# isd_main_lighting_board-v2.net
KiCad netlist of a schematic drawn in EAGLE
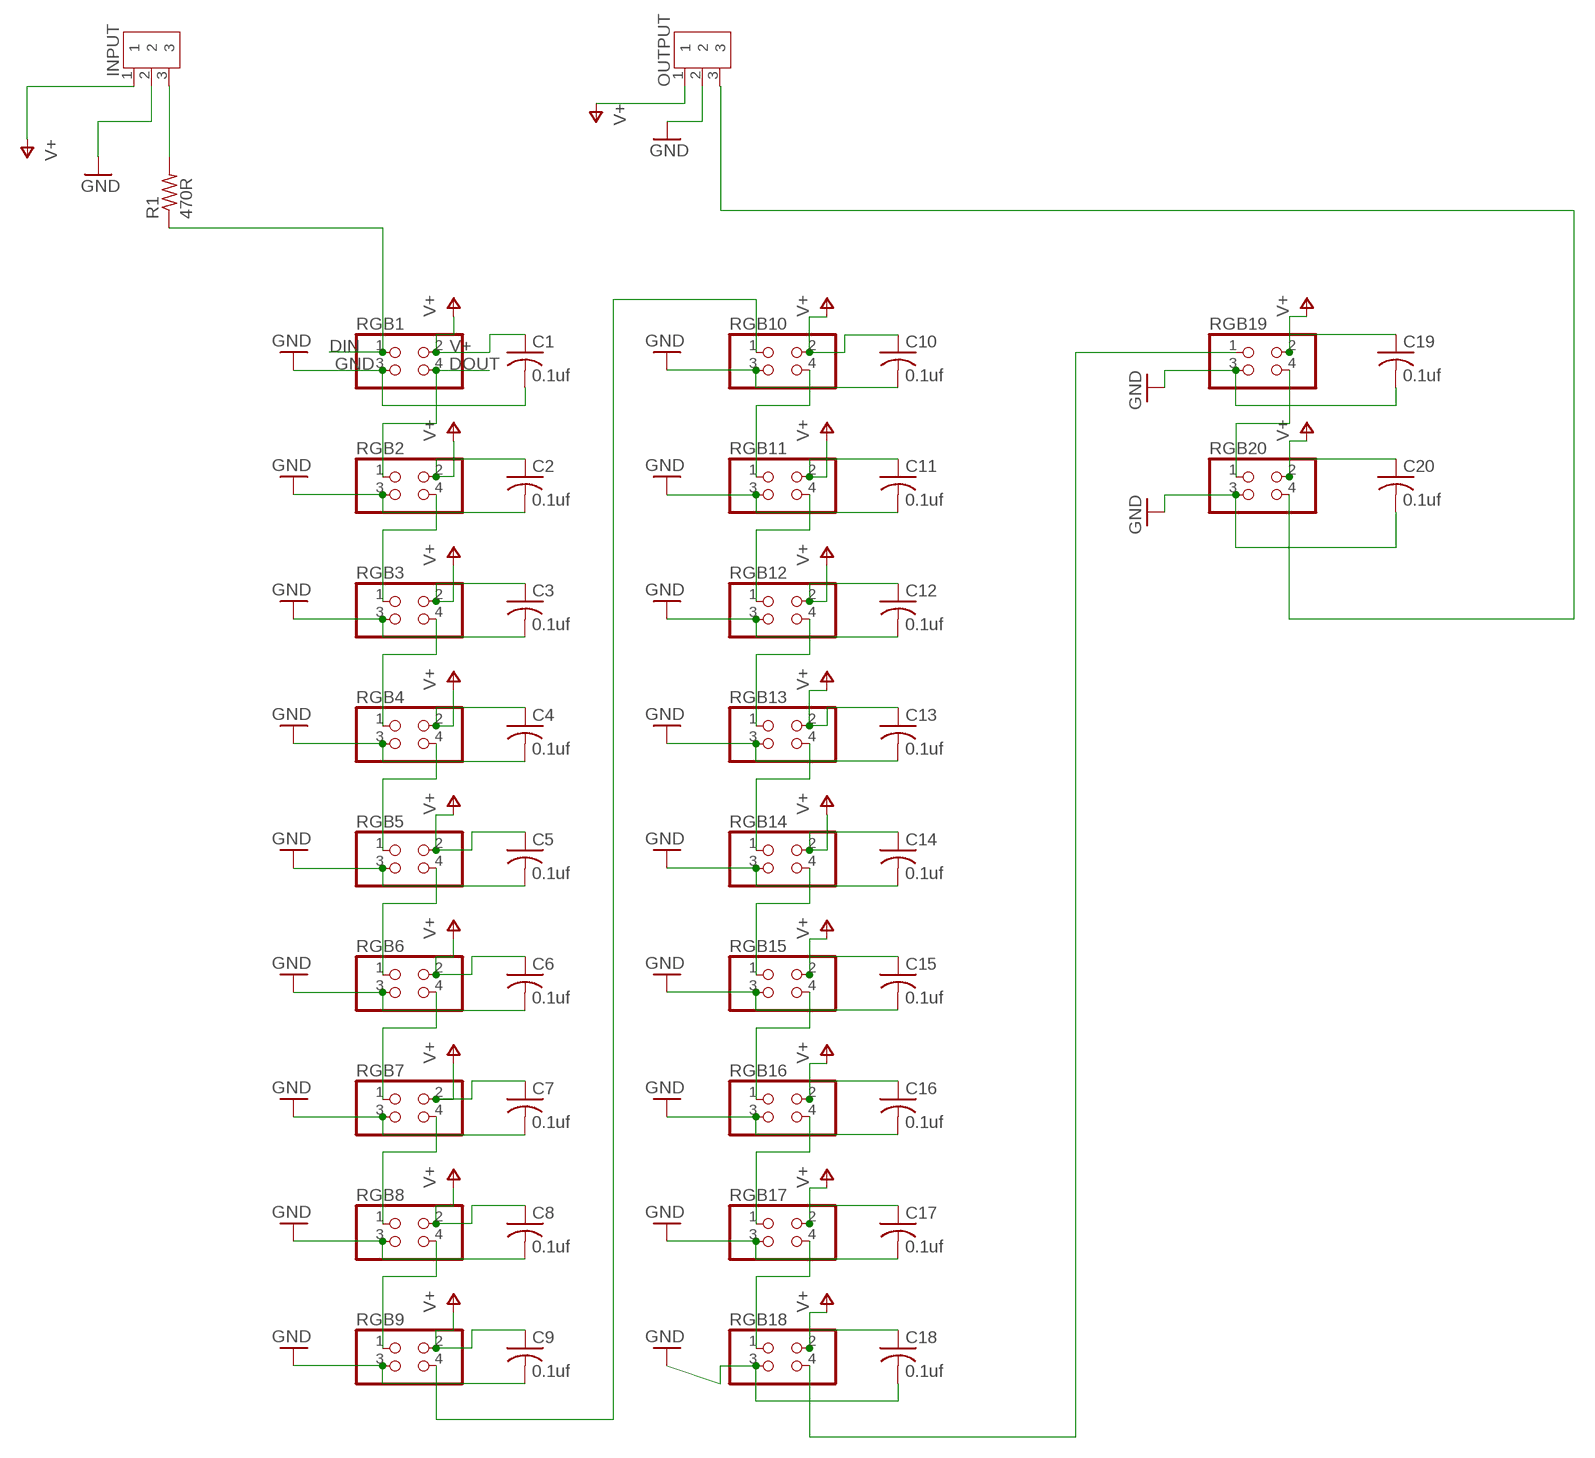
[diagram p0: schematic, sheet 1]

(export (version "E")
  (design (tool "Eeschema 10.0.6"))
  (components
    (comp (ref "C1")
      (value "0.1uf")
      (footprint "eagle-import:C0805")
      (libsource (lib "eagle-import") (part "C-USC0805"))
    )
    (comp (ref "C2")
      (value "0.1uf")
      (footprint "eagle-import:C0805")
      (libsource (lib "eagle-import") (part "C-USC0805"))
    )
    (comp (ref "C3")
      (value "0.1uf")
      (footprint "eagle-import:C0805")
      (libsource (lib "eagle-import") (part "C-USC0805"))
    )
    (comp (ref "C4")
      (value "0.1uf")
      (footprint "eagle-import:C0805")
      (libsource (lib "eagle-import") (part "C-USC0805"))
    )
    (comp (ref "C5")
      (value "0.1uf")
      (footprint "eagle-import:C0805")
      (libsource (lib "eagle-import") (part "C-USC0805"))
    )
    (comp (ref "C6")
      (value "0.1uf")
      (footprint "eagle-import:C0805")
      (libsource (lib "eagle-import") (part "C-USC0805"))
    )
    (comp (ref "C7")
      (value "0.1uf")
      (footprint "eagle-import:C0805")
      (libsource (lib "eagle-import") (part "C-USC0805"))
    )
    (comp (ref "C8")
      (value "0.1uf")
      (footprint "eagle-import:C0805")
      (libsource (lib "eagle-import") (part "C-USC0805"))
    )
    (comp (ref "C9")
      (value "0.1uf")
      (footprint "eagle-import:C0805")
      (libsource (lib "eagle-import") (part "C-USC0805"))
    )
    (comp (ref "C10")
      (value "0.1uf")
      (footprint "eagle-import:C0805")
      (libsource (lib "eagle-import") (part "C-USC0805"))
    )
    (comp (ref "C11")
      (value "0.1uf")
      (footprint "eagle-import:C0805")
      (libsource (lib "eagle-import") (part "C-USC0805"))
    )
    (comp (ref "C12")
      (value "0.1uf")
      (footprint "eagle-import:C0805")
      (libsource (lib "eagle-import") (part "C-USC0805"))
    )
    (comp (ref "C13")
      (value "0.1uf")
      (footprint "eagle-import:C0805")
      (libsource (lib "eagle-import") (part "C-USC0805"))
    )
    (comp (ref "C14")
      (value "0.1uf")
      (footprint "eagle-import:C0805")
      (libsource (lib "eagle-import") (part "C-USC0805"))
    )
    (comp (ref "C15")
      (value "0.1uf")
      (footprint "eagle-import:C0805")
      (libsource (lib "eagle-import") (part "C-USC0805"))
    )
    (comp (ref "C16")
      (value "0.1uf")
      (footprint "eagle-import:C0805")
      (libsource (lib "eagle-import") (part "C-USC0805"))
    )
    (comp (ref "C17")
      (value "0.1uf")
      (footprint "eagle-import:C0805")
      (libsource (lib "eagle-import") (part "C-USC0805"))
    )
    (comp (ref "C18")
      (value "0.1uf")
      (footprint "eagle-import:C0805")
      (libsource (lib "eagle-import") (part "C-USC0805"))
    )
    (comp (ref "C19")
      (value "0.1uf")
      (footprint "eagle-import:C0805")
      (libsource (lib "eagle-import") (part "C-USC0805"))
    )
    (comp (ref "C20")
      (value "0.1uf")
      (footprint "eagle-import:C0805")
      (libsource (lib "eagle-import") (part "C-USC0805"))
    )
    (comp (ref "INPUT")
      (value "B3B-XH-A")
      (footprint "eagle-import:B3B-XH-A")
      (fields (field (name "MANUFACTURER") "JST (XH connector)"))
      (libsource (lib "eagle-import") (part "B3B-XH-A"))
    )
    (comp (ref "OUTPUT")
      (value "B3B-XH-A")
      (footprint "eagle-import:B3B-XH-A")
      (fields (field (name "MANUFACTURER") "JST (XH connector)"))
      (libsource (lib "eagle-import") (part "B3B-XH-A"))
    )
    (comp (ref "R1")
      (value "470R")
      (footprint "eagle-import:0204_5")
      (libsource (lib "eagle-import") (part "R-US_0204/5"))
    )
    (comp (ref "RGB1")
      (value "PINHD-2X2")
      (footprint "eagle-import:2X02")
      (libsource (lib "eagle-import") (part "PINHD-2X2"))
    )
    (comp (ref "RGB2")
      (value "PINHD-2X2")
      (footprint "eagle-import:2X02")
      (libsource (lib "eagle-import") (part "PINHD-2X2"))
    )
    (comp (ref "RGB3")
      (value "PINHD-2X2")
      (footprint "eagle-import:2X02")
      (libsource (lib "eagle-import") (part "PINHD-2X2"))
    )
    (comp (ref "RGB4")
      (value "PINHD-2X2")
      (footprint "eagle-import:2X02")
      (libsource (lib "eagle-import") (part "PINHD-2X2"))
    )
    (comp (ref "RGB5")
      (value "PINHD-2X2")
      (footprint "eagle-import:2X02")
      (libsource (lib "eagle-import") (part "PINHD-2X2"))
    )
    (comp (ref "RGB6")
      (value "PINHD-2X2")
      (footprint "eagle-import:2X02")
      (libsource (lib "eagle-import") (part "PINHD-2X2"))
    )
    (comp (ref "RGB7")
      (value "PINHD-2X2")
      (footprint "eagle-import:2X02")
      (libsource (lib "eagle-import") (part "PINHD-2X2"))
    )
    (comp (ref "RGB8")
      (value "PINHD-2X2")
      (footprint "eagle-import:2X02")
      (libsource (lib "eagle-import") (part "PINHD-2X2"))
    )
    (comp (ref "RGB9")
      (value "PINHD-2X2")
      (footprint "eagle-import:2X02")
      (libsource (lib "eagle-import") (part "PINHD-2X2"))
    )
    (comp (ref "RGB10")
      (value "PINHD-2X2")
      (footprint "eagle-import:2X02")
      (libsource (lib "eagle-import") (part "PINHD-2X2"))
    )
    (comp (ref "RGB11")
      (value "PINHD-2X2")
      (footprint "eagle-import:2X02")
      (libsource (lib "eagle-import") (part "PINHD-2X2"))
    )
    (comp (ref "RGB12")
      (value "PINHD-2X2")
      (footprint "eagle-import:2X02")
      (libsource (lib "eagle-import") (part "PINHD-2X2"))
    )
    (comp (ref "RGB13")
      (value "PINHD-2X2")
      (footprint "eagle-import:2X02")
      (libsource (lib "eagle-import") (part "PINHD-2X2"))
    )
    (comp (ref "RGB14")
      (value "PINHD-2X2")
      (footprint "eagle-import:2X02")
      (libsource (lib "eagle-import") (part "PINHD-2X2"))
    )
    (comp (ref "RGB15")
      (value "PINHD-2X2")
      (footprint "eagle-import:2X02")
      (libsource (lib "eagle-import") (part "PINHD-2X2"))
    )
    (comp (ref "RGB16")
      (value "PINHD-2X2")
      (footprint "eagle-import:2X02")
      (libsource (lib "eagle-import") (part "PINHD-2X2"))
    )
    (comp (ref "RGB17")
      (value "PINHD-2X2")
      (footprint "eagle-import:2X02")
      (libsource (lib "eagle-import") (part "PINHD-2X2"))
    )
    (comp (ref "RGB18")
      (value "PINHD-2X2")
      (footprint "eagle-import:2X02")
      (libsource (lib "eagle-import") (part "PINHD-2X2"))
    )
    (comp (ref "RGB19")
      (value "PINHD-2X2")
      (footprint "eagle-import:2X02")
      (libsource (lib "eagle-import") (part "PINHD-2X2"))
    )
    (comp (ref "RGB20")
      (value "PINHD-2X2")
      (footprint "eagle-import:2X02")
      (libsource (lib "eagle-import") (part "PINHD-2X2"))
    )
  )
  (nets
    (net (code "1") (name "/DIN") (class "Default")
      (node (ref "R1") (pin "1") (pinfunction "1_1") (pintype "passive"))
      (node (ref "RGB1") (pin "1") (pinfunction "1_1") (pintype "passive"))
    )
    (net (code "2") (name "/DOUT") (class "Default")
      (node (ref "RGB1") (pin "4") (pinfunction "4_4") (pintype "passive"))
      (node (ref "RGB2") (pin "1") (pinfunction "1_1") (pintype "passive"))
    )
    (net (code "3") (name "GND") (class "Default")
      (node (ref "C1") (pin "2") (pinfunction "2_2") (pintype "passive"))
      (node (ref "C10") (pin "2") (pinfunction "2_2") (pintype "passive"))
      (node (ref "C11") (pin "2") (pinfunction "2_2") (pintype "passive"))
      (node (ref "C12") (pin "2") (pinfunction "2_2") (pintype "passive"))
      (node (ref "C13") (pin "2") (pinfunction "2_2") (pintype "passive"))
      (node (ref "C14") (pin "2") (pinfunction "2_2") (pintype "passive"))
      (node (ref "C15") (pin "2") (pinfunction "2_2") (pintype "passive"))
      (node (ref "C16") (pin "2") (pinfunction "2_2") (pintype "passive"))
      (node (ref "C17") (pin "2") (pinfunction "2_2") (pintype "passive"))
      (node (ref "C18") (pin "2") (pinfunction "2_2") (pintype "passive"))
      (node (ref "C19") (pin "2") (pinfunction "2_2") (pintype "passive"))
      (node (ref "C2") (pin "2") (pinfunction "2_2") (pintype "passive"))
      (node (ref "C20") (pin "2") (pinfunction "2_2") (pintype "passive"))
      (node (ref "C3") (pin "2") (pinfunction "2_2") (pintype "passive"))
      (node (ref "C4") (pin "2") (pinfunction "2_2") (pintype "passive"))
      (node (ref "C5") (pin "2") (pinfunction "2_2") (pintype "passive"))
      (node (ref "C6") (pin "2") (pinfunction "2_2") (pintype "passive"))
      (node (ref "C7") (pin "2") (pinfunction "2_2") (pintype "passive"))
      (node (ref "C8") (pin "2") (pinfunction "2_2") (pintype "passive"))
      (node (ref "C9") (pin "2") (pinfunction "2_2") (pintype "passive"))
      (node (ref "INPUT") (pin "2") (pinfunction "2_2") (pintype "bidirectional"))
      (node (ref "OUTPUT") (pin "2") (pinfunction "2_2") (pintype "bidirectional"))
      (node (ref "RGB1") (pin "3") (pinfunction "3_3") (pintype "passive"))
      (node (ref "RGB10") (pin "3") (pinfunction "3_3") (pintype "passive"))
      (node (ref "RGB11") (pin "3") (pinfunction "3_3") (pintype "passive"))
      (node (ref "RGB12") (pin "3") (pinfunction "3_3") (pintype "passive"))
      (node (ref "RGB13") (pin "3") (pinfunction "3_3") (pintype "passive"))
      (node (ref "RGB14") (pin "3") (pinfunction "3_3") (pintype "passive"))
      (node (ref "RGB15") (pin "3") (pinfunction "3_3") (pintype "passive"))
      (node (ref "RGB16") (pin "3") (pinfunction "3_3") (pintype "passive"))
      (node (ref "RGB17") (pin "3") (pinfunction "3_3") (pintype "passive"))
      (node (ref "RGB18") (pin "3") (pinfunction "3_3") (pintype "passive"))
      (node (ref "RGB19") (pin "3") (pinfunction "3_3") (pintype "passive"))
      (node (ref "RGB2") (pin "3") (pinfunction "3_3") (pintype "passive"))
      (node (ref "RGB20") (pin "3") (pinfunction "3_3") (pintype "passive"))
      (node (ref "RGB3") (pin "3") (pinfunction "3_3") (pintype "passive"))
      (node (ref "RGB4") (pin "3") (pinfunction "3_3") (pintype "passive"))
      (node (ref "RGB5") (pin "3") (pinfunction "3_3") (pintype "passive"))
      (node (ref "RGB6") (pin "3") (pinfunction "3_3") (pintype "passive"))
      (node (ref "RGB7") (pin "3") (pinfunction "3_3") (pintype "passive"))
      (node (ref "RGB8") (pin "3") (pinfunction "3_3") (pintype "passive"))
      (node (ref "RGB9") (pin "3") (pinfunction "3_3") (pintype "passive"))
    )
    (net (code "4") (name "Net-(INPUT-Pad3)") (class "Default")
      (node (ref "INPUT") (pin "3") (pinfunction "3_3") (pintype "bidirectional"))
      (node (ref "R1") (pin "2") (pinfunction "2_2") (pintype "passive"))
    )
    (net (code "5") (name "Net-(OUTPUT-Pad3)") (class "Default")
      (node (ref "OUTPUT") (pin "3") (pinfunction "3_3") (pintype "bidirectional"))
      (node (ref "RGB20") (pin "4") (pinfunction "4_4") (pintype "passive"))
    )
    (net (code "6") (name "Net-(RGB2-Pad4)") (class "Default")
      (node (ref "RGB2") (pin "4") (pinfunction "4_4") (pintype "passive"))
      (node (ref "RGB3") (pin "1") (pinfunction "1_1") (pintype "passive"))
    )
    (net (code "7") (name "Net-(RGB3-Pad4)") (class "Default")
      (node (ref "RGB3") (pin "4") (pinfunction "4_4") (pintype "passive"))
      (node (ref "RGB4") (pin "1") (pinfunction "1_1") (pintype "passive"))
    )
    (net (code "8") (name "Net-(RGB4-Pad4)") (class "Default")
      (node (ref "RGB4") (pin "4") (pinfunction "4_4") (pintype "passive"))
      (node (ref "RGB5") (pin "1") (pinfunction "1_1") (pintype "passive"))
    )
    (net (code "9") (name "Net-(RGB5-Pad4)") (class "Default")
      (node (ref "RGB5") (pin "4") (pinfunction "4_4") (pintype "passive"))
      (node (ref "RGB6") (pin "1") (pinfunction "1_1") (pintype "passive"))
    )
    (net (code "10") (name "Net-(RGB6-Pad4)") (class "Default")
      (node (ref "RGB6") (pin "4") (pinfunction "4_4") (pintype "passive"))
      (node (ref "RGB7") (pin "1") (pinfunction "1_1") (pintype "passive"))
    )
    (net (code "11") (name "Net-(RGB7-Pad4)") (class "Default")
      (node (ref "RGB7") (pin "4") (pinfunction "4_4") (pintype "passive"))
      (node (ref "RGB8") (pin "1") (pinfunction "1_1") (pintype "passive"))
    )
    (net (code "12") (name "Net-(RGB8-Pad4)") (class "Default")
      (node (ref "RGB8") (pin "4") (pinfunction "4_4") (pintype "passive"))
      (node (ref "RGB9") (pin "1") (pinfunction "1_1") (pintype "passive"))
    )
    (net (code "13") (name "Net-(RGB10-Pad1)") (class "Default")
      (node (ref "RGB10") (pin "1") (pinfunction "1_1") (pintype "passive"))
      (node (ref "RGB9") (pin "4") (pinfunction "4_4") (pintype "passive"))
    )
    (net (code "14") (name "Net-(RGB10-Pad4)") (class "Default")
      (node (ref "RGB10") (pin "4") (pinfunction "4_4") (pintype "passive"))
      (node (ref "RGB11") (pin "1") (pinfunction "1_1") (pintype "passive"))
    )
    (net (code "15") (name "Net-(RGB11-Pad4)") (class "Default")
      (node (ref "RGB11") (pin "4") (pinfunction "4_4") (pintype "passive"))
      (node (ref "RGB12") (pin "1") (pinfunction "1_1") (pintype "passive"))
    )
    (net (code "16") (name "Net-(RGB12-Pad4)") (class "Default")
      (node (ref "RGB12") (pin "4") (pinfunction "4_4") (pintype "passive"))
      (node (ref "RGB13") (pin "1") (pinfunction "1_1") (pintype "passive"))
    )
    (net (code "17") (name "Net-(RGB13-Pad4)") (class "Default")
      (node (ref "RGB13") (pin "4") (pinfunction "4_4") (pintype "passive"))
      (node (ref "RGB14") (pin "1") (pinfunction "1_1") (pintype "passive"))
    )
    (net (code "18") (name "Net-(RGB14-Pad4)") (class "Default")
      (node (ref "RGB14") (pin "4") (pinfunction "4_4") (pintype "passive"))
      (node (ref "RGB15") (pin "1") (pinfunction "1_1") (pintype "passive"))
    )
    (net (code "19") (name "Net-(RGB15-Pad4)") (class "Default")
      (node (ref "RGB15") (pin "4") (pinfunction "4_4") (pintype "passive"))
      (node (ref "RGB16") (pin "1") (pinfunction "1_1") (pintype "passive"))
    )
    (net (code "20") (name "Net-(RGB16-Pad4)") (class "Default")
      (node (ref "RGB16") (pin "4") (pinfunction "4_4") (pintype "passive"))
      (node (ref "RGB17") (pin "1") (pinfunction "1_1") (pintype "passive"))
    )
    (net (code "21") (name "Net-(RGB17-Pad4)") (class "Default")
      (node (ref "RGB17") (pin "4") (pinfunction "4_4") (pintype "passive"))
      (node (ref "RGB18") (pin "1") (pinfunction "1_1") (pintype "passive"))
    )
    (net (code "22") (name "Net-(RGB18-Pad4)") (class "Default")
      (node (ref "RGB18") (pin "4") (pinfunction "4_4") (pintype "passive"))
      (node (ref "RGB19") (pin "1") (pinfunction "1_1") (pintype "passive"))
    )
    (net (code "23") (name "Net-(RGB19-Pad4)") (class "Default")
      (node (ref "RGB19") (pin "4") (pinfunction "4_4") (pintype "passive"))
      (node (ref "RGB20") (pin "1") (pinfunction "1_1") (pintype "passive"))
    )
    (net (code "24") (name "V+") (class "Default")
      (node (ref "C1") (pin "1") (pinfunction "1_1") (pintype "passive"))
      (node (ref "C10") (pin "1") (pinfunction "1_1") (pintype "passive"))
      (node (ref "C11") (pin "1") (pinfunction "1_1") (pintype "passive"))
      (node (ref "C12") (pin "1") (pinfunction "1_1") (pintype "passive"))
      (node (ref "C13") (pin "1") (pinfunction "1_1") (pintype "passive"))
      (node (ref "C14") (pin "1") (pinfunction "1_1") (pintype "passive"))
      (node (ref "C15") (pin "1") (pinfunction "1_1") (pintype "passive"))
      (node (ref "C16") (pin "1") (pinfunction "1_1") (pintype "passive"))
      (node (ref "C17") (pin "1") (pinfunction "1_1") (pintype "passive"))
      (node (ref "C18") (pin "1") (pinfunction "1_1") (pintype "passive"))
      (node (ref "C19") (pin "1") (pinfunction "1_1") (pintype "passive"))
      (node (ref "C2") (pin "1") (pinfunction "1_1") (pintype "passive"))
      (node (ref "C20") (pin "1") (pinfunction "1_1") (pintype "passive"))
      (node (ref "C3") (pin "1") (pinfunction "1_1") (pintype "passive"))
      (node (ref "C4") (pin "1") (pinfunction "1_1") (pintype "passive"))
      (node (ref "C5") (pin "1") (pinfunction "1_1") (pintype "passive"))
      (node (ref "C6") (pin "1") (pinfunction "1_1") (pintype "passive"))
      (node (ref "C7") (pin "1") (pinfunction "1_1") (pintype "passive"))
      (node (ref "C8") (pin "1") (pinfunction "1_1") (pintype "passive"))
      (node (ref "C9") (pin "1") (pinfunction "1_1") (pintype "passive"))
      (node (ref "INPUT") (pin "1") (pinfunction "1_1") (pintype "bidirectional"))
      (node (ref "OUTPUT") (pin "1") (pinfunction "1_1") (pintype "bidirectional"))
      (node (ref "RGB1") (pin "2") (pinfunction "2_2") (pintype "passive"))
      (node (ref "RGB10") (pin "2") (pinfunction "2_2") (pintype "passive"))
      (node (ref "RGB11") (pin "2") (pinfunction "2_2") (pintype "passive"))
      (node (ref "RGB12") (pin "2") (pinfunction "2_2") (pintype "passive"))
      (node (ref "RGB13") (pin "2") (pinfunction "2_2") (pintype "passive"))
      (node (ref "RGB14") (pin "2") (pinfunction "2_2") (pintype "passive"))
      (node (ref "RGB15") (pin "2") (pinfunction "2_2") (pintype "passive"))
      (node (ref "RGB16") (pin "2") (pinfunction "2_2") (pintype "passive"))
      (node (ref "RGB17") (pin "2") (pinfunction "2_2") (pintype "passive"))
      (node (ref "RGB18") (pin "2") (pinfunction "2_2") (pintype "passive"))
      (node (ref "RGB19") (pin "2") (pinfunction "2_2") (pintype "passive"))
      (node (ref "RGB2") (pin "2") (pinfunction "2_2") (pintype "passive"))
      (node (ref "RGB20") (pin "2") (pinfunction "2_2") (pintype "passive"))
      (node (ref "RGB3") (pin "2") (pinfunction "2_2") (pintype "passive"))
      (node (ref "RGB4") (pin "2") (pinfunction "2_2") (pintype "passive"))
      (node (ref "RGB5") (pin "2") (pinfunction "2_2") (pintype "passive"))
      (node (ref "RGB6") (pin "2") (pinfunction "2_2") (pintype "passive"))
      (node (ref "RGB7") (pin "2") (pinfunction "2_2") (pintype "passive"))
      (node (ref "RGB8") (pin "2") (pinfunction "2_2") (pintype "passive"))
      (node (ref "RGB9") (pin "2") (pinfunction "2_2") (pintype "passive"))
    )
  )
)
